# MCO_controller_V5.net
KiCad netlist of a schematic drawn in EAGLE
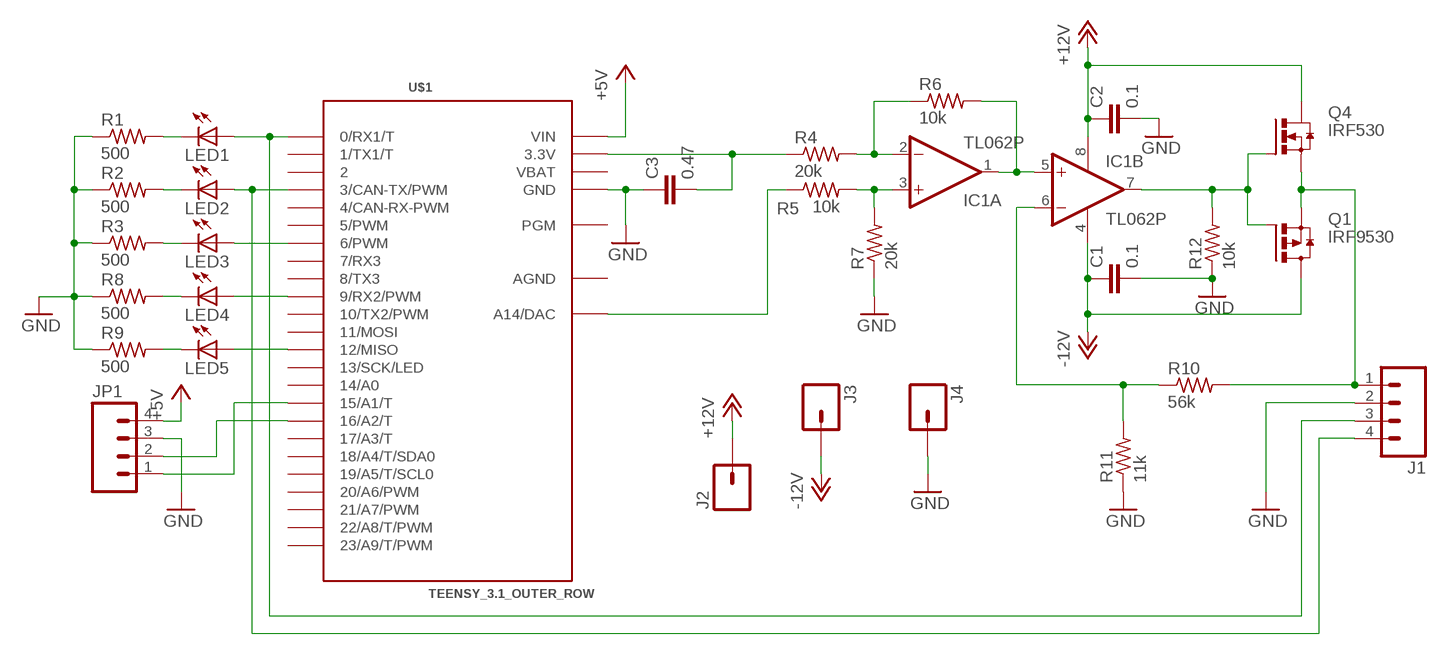
[diagram p0: schematic, sheet 1]

(export (version "E")
  (design (tool "Eeschema 10.0.6"))
  (components
    (comp (ref "C1")
      (value "0.1")
      (footprint "eagle-import:CAP-PTH-SMALL")
      (libsource (lib "eagle-import") (part "CAPPTH"))
    )
    (comp (ref "C2")
      (value "0.1")
      (footprint "eagle-import:CAP-PTH-SMALL")
      (libsource (lib "eagle-import") (part "CAPPTH"))
    )
    (comp (ref "C3")
      (value "0.47")
      (footprint "eagle-import:CAP-PTH-5MM")
      (libsource (lib "eagle-import") (part "CAPPTH1"))
    )
    (comp (ref "IC1")
      (value "TL062P")
      (footprint "eagle-import:DIL08")
      (libsource (lib "eagle-import") (part "TL062P"))
    )
    (comp (ref "J1")
      (value "M04SCREW")
      (footprint "eagle-import:SCREWTERMINAL-3.5MM-4")
      (libsource (lib "eagle-import") (part "SparkFun-Connectors_M04SCREW"))
    )
    (comp (ref "J2")
      (value "M01PTH_LONGPAD")
      (footprint "eagle-import:1X01_LONGPAD")
      (libsource (lib "eagle-import") (part "M01PTH_LONGPAD"))
    )
    (comp (ref "J3")
      (value "M01PTH_LONGPAD")
      (footprint "eagle-import:1X01_LONGPAD")
      (libsource (lib "eagle-import") (part "M01PTH_LONGPAD"))
    )
    (comp (ref "J4")
      (value "M01PTH_LONGPAD")
      (footprint "eagle-import:1X01_LONGPAD")
      (libsource (lib "eagle-import") (part "M01PTH_LONGPAD"))
    )
    (comp (ref "JP1")
      (value "M04SCREW")
      (footprint "eagle-import:SCREWTERMINAL-3.5MM-4")
      (libsource (lib "eagle-import") (part "M04SCREW"))
    )
    (comp (ref "LED1")
      (value "LED5MM")
      (footprint "eagle-import:LED5MM")
      (libsource (lib "eagle-import") (part "LED5MM"))
    )
    (comp (ref "LED2")
      (value "LED5MM")
      (footprint "eagle-import:LED5MM")
      (libsource (lib "eagle-import") (part "LED5MM"))
    )
    (comp (ref "LED3")
      (value "LED5MM")
      (footprint "eagle-import:LED5MM")
      (libsource (lib "eagle-import") (part "LED5MM"))
    )
    (comp (ref "LED4")
      (value "LED5MM")
      (footprint "eagle-import:LED5MM")
      (libsource (lib "eagle-import") (part "LED5MM"))
    )
    (comp (ref "LED5")
      (value "LED5MM")
      (footprint "eagle-import:LED5MM")
      (libsource (lib "eagle-import") (part "LED5MM"))
    )
    (comp (ref "Q1")
      (value "IRF9530")
      (footprint "eagle-import:TO220AV")
      (libsource (lib "eagle-import") (part "IRF9530"))
    )
    (comp (ref "Q4")
      (value "IRF530")
      (footprint "eagle-import:TO220AV")
      (libsource (lib "eagle-import") (part "IRF530"))
    )
    (comp (ref "R1")
      (value "500")
      (footprint "eagle-import:0207_10")
      (libsource (lib "eagle-import") (part "R-US_0207/10"))
    )
    (comp (ref "R2")
      (value "500")
      (footprint "eagle-import:0207_10")
      (libsource (lib "eagle-import") (part "R-US_0207/10"))
    )
    (comp (ref "R3")
      (value "500")
      (footprint "eagle-import:0207_10")
      (libsource (lib "eagle-import") (part "R-US_0207/10"))
    )
    (comp (ref "R4")
      (value "20k")
      (footprint "eagle-import:0207_10")
      (libsource (lib "eagle-import") (part "R-US_0207/10"))
    )
    (comp (ref "R5")
      (value "10k")
      (footprint "eagle-import:0207_10")
      (libsource (lib "eagle-import") (part "R-US_0207/10"))
    )
    (comp (ref "R6")
      (value "10k")
      (footprint "eagle-import:0207_10")
      (libsource (lib "eagle-import") (part "R-US_0207/10"))
    )
    (comp (ref "R7")
      (value "20k")
      (footprint "eagle-import:0207_10")
      (libsource (lib "eagle-import") (part "R-US_0207/10"))
    )
    (comp (ref "R8")
      (value "500")
      (footprint "eagle-import:0207_10")
      (libsource (lib "eagle-import") (part "R-US_0207/10"))
    )
    (comp (ref "R9")
      (value "500")
      (footprint "eagle-import:0207_10")
      (libsource (lib "eagle-import") (part "R-US_0207/10"))
    )
    (comp (ref "R10")
      (value "56k")
      (footprint "eagle-import:0207_10")
      (libsource (lib "eagle-import") (part "R-US_0207/10"))
    )
    (comp (ref "R11")
      (value "11k")
      (footprint "eagle-import:0207_10")
      (libsource (lib "eagle-import") (part "R-US_0207/10"))
    )
    (comp (ref "R12")
      (value "10k")
      (footprint "eagle-import:0207_10")
      (libsource (lib "eagle-import") (part "R-US_0207/10"))
    )
    (comp (ref "U$1")
      (value "TEENSY_3.1_OUTER_ROW")
      (footprint "eagle-import:TEENSY3-OUTER_ROW")
      (libsource (lib "eagle-import") (part "TEENSY_3.1_OUTER_ROW"))
    )
  )
  (nets
    (net (code "1") (name "+5V") (class "Default")
      (node (ref "JP1") (pin "4") (pinfunction "4_4") (pintype "passive"))
      (node (ref "U$1") (pin "VIN") (pinfunction "VIN_VIN") (pintype "power_in"))
    )
    (net (code "2") (name "+12V") (class "Default")
      (node (ref "C2") (pin "1") (pinfunction "1_1") (pintype "passive"))
      (node (ref "IC1") (pin "8") (pinfunction "V+_8") (pintype "power_in"))
      (node (ref "J2") (pin "1") (pinfunction "1_1") (pintype "passive"))
      (node (ref "Q4") (pin "C") (pinfunction "D_C") (pintype "passive"))
    )
    (net (code "3") (name "-12V") (class "Default")
      (node (ref "C1") (pin "1") (pinfunction "1_1") (pintype "passive"))
      (node (ref "IC1") (pin "4") (pinfunction "V-_4") (pintype "power_in"))
      (node (ref "J3") (pin "1") (pinfunction "1_1") (pintype "passive"))
      (node (ref "Q1") (pin "C") (pinfunction "D_C") (pintype "passive"))
    )
    (net (code "4") (name "/AGND") (class "Default")
      (node (ref "U$1") (pin "AGND") (pinfunction "AGND_AGND") (pintype "power_in"))
    )
    (net (code "5") (name "/VBAT") (class "Default")
      (node (ref "U$1") (pin "VBAT") (pinfunction "VBAT_VBAT") (pintype "power_in"))
    )
    (net (code "6") (name "GND") (class "Default")
      (node (ref "C1") (pin "2") (pinfunction "2_2") (pintype "passive"))
      (node (ref "C2") (pin "2") (pinfunction "2_2") (pintype "passive"))
      (node (ref "C3") (pin "1") (pinfunction "1_1") (pintype "passive"))
      (node (ref "J1") (pin "2") (pinfunction "2_2") (pintype "passive"))
      (node (ref "J4") (pin "1") (pinfunction "1_1") (pintype "passive"))
      (node (ref "JP1") (pin "3") (pinfunction "3_3") (pintype "passive"))
      (node (ref "R1") (pin "1") (pinfunction "1_1") (pintype "passive"))
      (node (ref "R11") (pin "1") (pinfunction "1_1") (pintype "passive"))
      (node (ref "R12") (pin "1") (pinfunction "1_1") (pintype "passive"))
      (node (ref "R2") (pin "1") (pinfunction "1_1") (pintype "passive"))
      (node (ref "R3") (pin "1") (pinfunction "1_1") (pintype "passive"))
      (node (ref "R7") (pin "1") (pinfunction "1_1") (pintype "passive"))
      (node (ref "R8") (pin "1") (pinfunction "1_1") (pintype "passive"))
      (node (ref "R9") (pin "1") (pinfunction "1_1") (pintype "passive"))
      (node (ref "U$1") (pin "GND") (pinfunction "GND_GND") (pintype "power_in"))
      (node (ref "U$1") (pin "GND1") (pinfunction "GND_GND1") (pintype "power_in"))
    )
    (net (code "7") (name "Net-(C3-Pad2)") (class "Default")
      (node (ref "C3") (pin "2") (pinfunction "2_2") (pintype "passive"))
      (node (ref "R4") (pin "1") (pinfunction "1_1") (pintype "passive"))
      (node (ref "U$1") (pin "3.3V") (pinfunction "3.3V_3.3V") (pintype "power_in"))
      (node (ref "U$1") (pin "3.3V1") (pinfunction "3.3V_3.3V1") (pintype "power_in"))
    )
    (net (code "8") (name "Net-(IC1A-+IN)") (class "Default")
      (node (ref "IC1") (pin "3") (pinfunction "+IN_3") (pintype "input"))
      (node (ref "R5") (pin "2") (pinfunction "2_2") (pintype "passive"))
      (node (ref "R7") (pin "2") (pinfunction "2_2") (pintype "passive"))
    )
    (net (code "9") (name "Net-(IC1A--IN)") (class "Default")
      (node (ref "IC1") (pin "2") (pinfunction "-IN_2") (pintype "input"))
      (node (ref "R4") (pin "2") (pinfunction "2_2") (pintype "passive"))
      (node (ref "R6") (pin "1") (pinfunction "1_1") (pintype "passive"))
    )
    (net (code "10") (name "Net-(IC1A-OUT)") (class "Default")
      (node (ref "IC1") (pin "1") (pinfunction "OUT_1") (pintype "output"))
      (node (ref "IC1") (pin "5") (pinfunction "+IN_5") (pintype "input"))
      (node (ref "R6") (pin "2") (pinfunction "2_2") (pintype "passive"))
    )
    (net (code "11") (name "Net-(IC1B--IN)") (class "Default")
      (node (ref "IC1") (pin "6") (pinfunction "-IN_6") (pintype "input"))
      (node (ref "R10") (pin "1") (pinfunction "1_1") (pintype "passive"))
      (node (ref "R11") (pin "2") (pinfunction "2_2") (pintype "passive"))
    )
    (net (code "12") (name "Net-(IC1B-OUT)") (class "Default")
      (node (ref "IC1") (pin "7") (pinfunction "OUT_7") (pintype "output"))
      (node (ref "Q1") (pin "B") (pinfunction "G_B") (pintype "passive"))
      (node (ref "Q4") (pin "B") (pinfunction "G_B") (pintype "passive"))
      (node (ref "R12") (pin "2") (pinfunction "2_2") (pintype "passive"))
    )
    (net (code "13") (name "Net-(LED1-C)") (class "Default")
      (node (ref "LED1") (pin "K") (pinfunction "C_K") (pintype "passive"))
      (node (ref "R1") (pin "2") (pinfunction "2_2") (pintype "passive"))
    )
    (net (code "14") (name "Net-(LED2-C)") (class "Default")
      (node (ref "LED2") (pin "K") (pinfunction "C_K") (pintype "passive"))
      (node (ref "R2") (pin "2") (pinfunction "2_2") (pintype "passive"))
    )
    (net (code "15") (name "Net-(LED3-C)") (class "Default")
      (node (ref "LED3") (pin "K") (pinfunction "C_K") (pintype "passive"))
      (node (ref "R3") (pin "2") (pinfunction "2_2") (pintype "passive"))
    )
    (net (code "16") (name "Net-(LED4-C)") (class "Default")
      (node (ref "LED4") (pin "K") (pinfunction "C_K") (pintype "passive"))
      (node (ref "R8") (pin "2") (pinfunction "2_2") (pintype "passive"))
    )
    (net (code "17") (name "Net-(LED5-C)") (class "Default")
      (node (ref "LED5") (pin "K") (pinfunction "C_K") (pintype "passive"))
      (node (ref "R9") (pin "2") (pinfunction "2_2") (pintype "passive"))
    )
    (net (code "18") (name "Net-(Q1-S)") (class "Default")
      (node (ref "J1") (pin "1") (pinfunction "1_1") (pintype "passive"))
      (node (ref "Q1") (pin "E") (pinfunction "S_E") (pintype "passive"))
      (node (ref "Q4") (pin "E") (pinfunction "S_E") (pintype "passive"))
      (node (ref "R10") (pin "2") (pinfunction "2_2") (pintype "passive"))
    )
    (net (code "19") (name "Net-(U$1-0{slash}RX1{slash}T)") (class "Default")
      (node (ref "J1") (pin "3") (pinfunction "3_3") (pintype "passive"))
      (node (ref "LED1") (pin "A") (pinfunction "A_A") (pintype "passive"))
      (node (ref "U$1") (pin "0") (pinfunction "0/RX1/T_0") (pintype "bidirectional"))
    )
    (net (code "20") (name "Net-(U$1-3{slash}CAN-TX{slash}PWM)") (class "Default")
      (node (ref "J1") (pin "4") (pinfunction "4_4") (pintype "passive"))
      (node (ref "LED2") (pin "A") (pinfunction "A_A") (pintype "passive"))
      (node (ref "U$1") (pin "3") (pinfunction "3/CAN-TX/PWM_3") (pintype "bidirectional"))
    )
    (net (code "21") (name "Net-(U$1-6{slash}PWM)") (class "Default")
      (node (ref "LED3") (pin "A") (pinfunction "A_A") (pintype "passive"))
      (node (ref "U$1") (pin "6") (pinfunction "6/PWM_6") (pintype "bidirectional"))
    )
    (net (code "22") (name "Net-(U$1-9{slash}RX2{slash}PWM)") (class "Default")
      (node (ref "LED4") (pin "A") (pinfunction "A_A") (pintype "passive"))
      (node (ref "U$1") (pin "9") (pinfunction "9/RX2/PWM_9") (pintype "bidirectional"))
    )
    (net (code "23") (name "Net-(U$1-12{slash}MISO)") (class "Default")
      (node (ref "LED5") (pin "A") (pinfunction "A_A") (pintype "passive"))
      (node (ref "U$1") (pin "12") (pinfunction "12/MISO_12") (pintype "bidirectional"))
    )
    (net (code "24") (name "Net-(U$1-15{slash}A1{slash}T)") (class "Default")
      (node (ref "JP1") (pin "1") (pinfunction "1_1") (pintype "passive"))
      (node (ref "U$1") (pin "15/A1") (pinfunction "15/A1/T_15/A1") (pintype "bidirectional"))
    )
    (net (code "25") (name "Net-(U$1-16{slash}A2{slash}T)") (class "Default")
      (node (ref "JP1") (pin "2") (pinfunction "2_2") (pintype "passive"))
      (node (ref "U$1") (pin "16/A2") (pinfunction "16/A2/T_16/A2") (pintype "bidirectional"))
    )
    (net (code "26") (name "Net-(U$1-A14{slash}DAC)") (class "Default")
      (node (ref "R5") (pin "1") (pinfunction "1_1") (pintype "passive"))
      (node (ref "U$1") (pin "RESET/DAC") (pinfunction "A14/DAC_RESET/DAC") (pintype "bidirectional"))
    )
    (net (code "27") (name "unconnected-(U$1-1{slash}TX1{slash}T-Pad1)") (class "Default")
      (node (ref "U$1") (pin "1") (pinfunction "1/TX1/T_1") (pintype "bidirectional"))
    )
    (net (code "28") (name "unconnected-(U$1-4{slash}CAN-RX-PWM-Pad4)") (class "Default")
      (node (ref "U$1") (pin "4") (pinfunction "4/CAN-RX-PWM_4") (pintype "bidirectional"))
    )
    (net (code "29") (name "unconnected-(U$1-5{slash}PWM-Pad5)") (class "Default")
      (node (ref "U$1") (pin "5") (pinfunction "5/PWM_5") (pintype "bidirectional"))
    )
    (net (code "30") (name "unconnected-(U$1-7{slash}RX3-Pad7)") (class "Default")
      (node (ref "U$1") (pin "7") (pinfunction "7/RX3_7") (pintype "bidirectional"))
    )
    (net (code "31") (name "unconnected-(U$1-8{slash}TX3-Pad8)") (class "Default")
      (node (ref "U$1") (pin "8") (pinfunction "8/TX3_8") (pintype "bidirectional"))
    )
    (net (code "32") (name "unconnected-(U$1-10{slash}TX2{slash}PWM-Pad10)") (class "Default")
      (node (ref "U$1") (pin "10") (pinfunction "10/TX2/PWM_10") (pintype "bidirectional"))
    )
    (net (code "33") (name "unconnected-(U$1-11{slash}MOSI-Pad11)") (class "Default")
      (node (ref "U$1") (pin "11") (pinfunction "11/MOSI_11") (pintype "bidirectional"))
    )
    (net (code "34") (name "unconnected-(U$1-13{slash}SCK{slash}LED-Pad13)") (class "Default")
      (node (ref "U$1") (pin "13") (pinfunction "13/SCK/LED_13") (pintype "bidirectional"))
    )
    (net (code "35") (name "unconnected-(U$1-17{slash}A3{slash}T-Pad17{slash}A3)") (class "Default")
      (node (ref "U$1") (pin "17/A3") (pinfunction "17/A3/T_17/A3") (pintype "bidirectional"))
    )
    (net (code "36") (name "unconnected-(U$1-18{slash}A4{slash}T{slash}SDA0-Pad18{slash}A4)") (class "Default")
      (node (ref "U$1") (pin "18/A4") (pinfunction "18/A4/T/SDA0_18/A4") (pintype "bidirectional"))
    )
    (net (code "37") (name "unconnected-(U$1-19{slash}A5{slash}T{slash}SCL0-Pad19{slash}A5)") (class "Default")
      (node (ref "U$1") (pin "19/A5") (pinfunction "19/A5/T/SCL0_19/A5") (pintype "bidirectional"))
    )
    (net (code "38") (name "unconnected-(U$1-20{slash}A6{slash}PWM-Pad20{slash}A6)") (class "Default")
      (node (ref "U$1") (pin "20/A6") (pinfunction "20/A6/PWM_20/A6") (pintype "bidirectional"))
    )
    (net (code "39") (name "unconnected-(U$1-21{slash}A7{slash}PWM-Pad21{slash}A7)") (class "Default")
      (node (ref "U$1") (pin "21/A7") (pinfunction "21/A7/PWM_21/A7") (pintype "bidirectional"))
    )
    (net (code "40") (name "unconnected-(U$1-22{slash}A8{slash}T{slash}PWM-Pad22{slash}A8)") (class "Default")
      (node (ref "U$1") (pin "22/A8") (pinfunction "22/A8/T/PWM_22/A8") (pintype "bidirectional"))
    )
    (net (code "41") (name "unconnected-(U$1-23{slash}A9{slash}T{slash}PWM-Pad23{slash}A9)") (class "Default")
      (node (ref "U$1") (pin "23/A9") (pinfunction "23/A9/T/PWM_23/A9") (pintype "bidirectional"))
    )
    (net (code "42") (name "unconnected-(U$1-Pad2)") (class "Default")
      (node (ref "U$1") (pin "2") (pinfunction "2_2") (pintype "bidirectional"))
    )
    (net (code "43") (name "unconnected-(U$1-Pad14{slash}A0)") (class "Default")
      (node (ref "U$1") (pin "14/A0") (pinfunction "14/A0_14/A0") (pintype "bidirectional"))
    )
    (net (code "44") (name "unconnected-(U$1-PadPGM)") (class "Default")
      (node (ref "U$1") (pin "PGM") (pinfunction "PGM_PGM") (pintype "bidirectional"))
    )
  )
)
